# 6_FE-MISC.net
KiCad netlist of a schematic drawn in Altium Designer
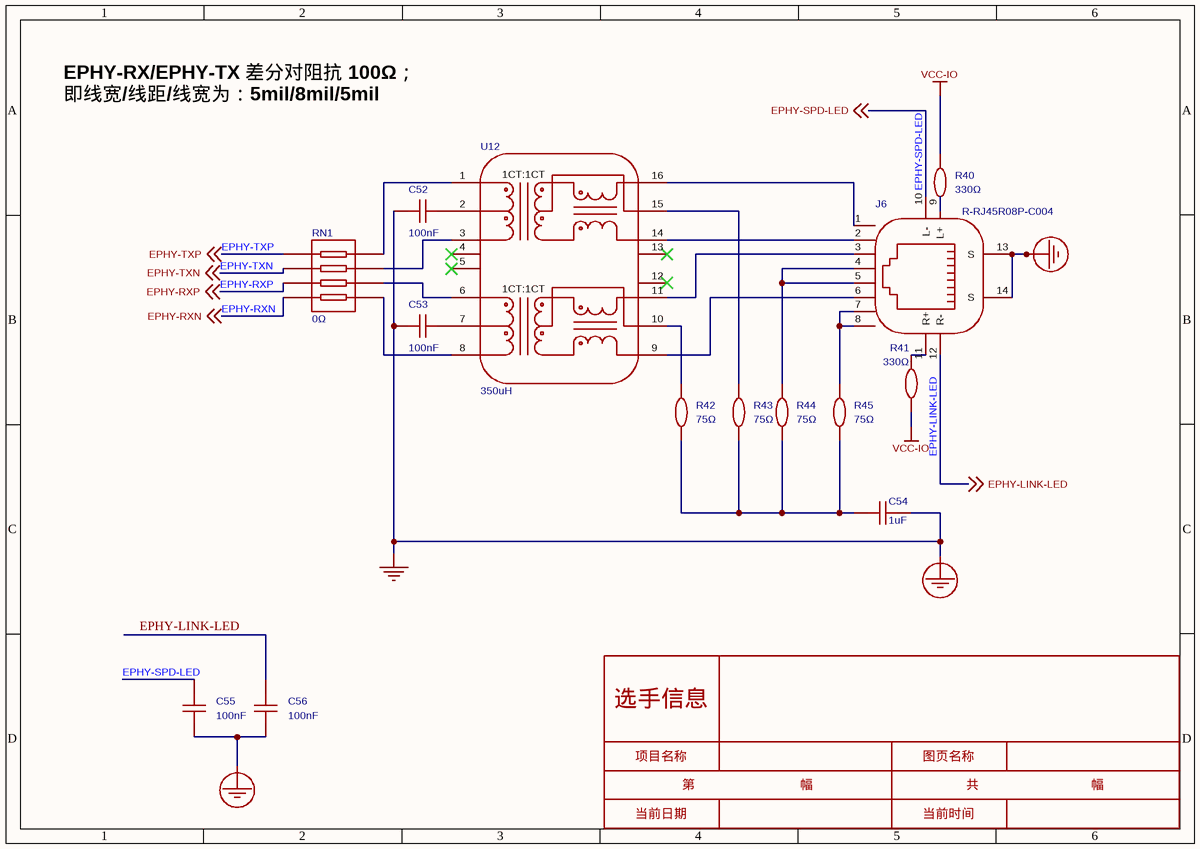
[diagram p0: 6_FE-MISC.schdoc]

(export (version "E")
  (design (tool "Eeschema 10.0.6"))
  (components
    (comp (ref "C52")
      (value "100nF")
      (footprint "C0402")
      (description "容值:100nF;精度:±10%;额定电压:16V;温度系数:X7R;")
      (fields
        (field (name "MANUFACTURER") "SAMSUNG(三星)")
        (field (name "MANUFACTURER PART") "CL05B104KO5NNNC")
      )
      (libsource (lib "altium-import") (part "root_2_CL05B104KO5NNNC_"))
    )
    (comp (ref "C53")
      (value "100nF")
      (footprint "C0402")
      (description "容值:100nF;精度:±10%;额定电压:16V;温度系数:X7R;")
      (fields
        (field (name "MANUFACTURER") "SAMSUNG(三星)")
        (field (name "MANUFACTURER PART") "CL05B104KO5NNNC")
      )
      (libsource (lib "altium-import") (part "root_2_CL05B104KO5NNNC_"))
    )
    (comp (ref "C54")
      (value "1uF")
      (footprint "C1206")
      (description "容值:1uF;精度:±10%;额定电压:50V;温度系数:X7R;")
      (fields (field (name "MANUFACTURER") "SAMSUNG(三星)") (field (name "MANUFACTURERPART") "CL31B105KBHNNNE"))
      (libsource (lib "altium-import") (part "root_0_CL31B105KBHNNNE_"))
    )
    (comp (ref "C55")
      (value "100nF")
      (footprint "C0402")
      (description "容值:100nF;精度:±10%;额定电压:16V;温度系数:X7R;")
      (fields
        (field (name "MANUFACTURER") "SAMSUNG(三星)")
        (field (name "MANUFACTURER PART") "CL05B104KO5NNNC")
      )
      (libsource (lib "altium-import") (part "root_1_CL05B104KO5NNNC_"))
    )
    (comp (ref "C56")
      (value "100nF")
      (footprint "C0402")
      (description "容值:100nF;精度:±10%;额定电压:16V;温度系数:X7R;")
      (fields
        (field (name "MANUFACTURER") "SAMSUNG(三星)")
        (field (name "MANUFACTURER PART") "CL05B104KO5NNNC")
      )
      (libsource (lib "altium-import") (part "root_1_CL05B104KO5NNNC_"))
    )
    (comp (ref "J6")
      (value "R-RJ45R08P-C004")
      (footprint "RJ45-TH_R-RJ45R08P-C004")
      (description "连接器类型:RJ45插座;安装方式:弯插;端口数量:1;LED:带LED;屏蔽:有屏蔽;等级:-;触头材质:磷青铜;触头镀层:金;工作温度:0℃~+70℃;")
      (fields (field (name "MANUFACTURER") "Ckmtw(灿科盟)"))
      (libsource (lib "altium-import") (part "root_3_R-RJ45R08P-C004_"))
    )
    (comp (ref "R40")
      (value "330Ω")
      (footprint "R0402")
      (description "电阻类型:厚膜电阻;阻值:330Ω;精度:±1%;功率:62.5mW;工作电压:50V;温度系数:±100ppm/℃;")
      (fields
        (field (name "MANUFACTURER") "UNI-ROYAL(厚声)")
        (field (name "MANUFACTURER PART") "0402WGF3300TCE")
      )
      (libsource (lib "altium-import") (part "root_3_0402WGF3300TCE_"))
    )
    (comp (ref "R41")
      (value "330Ω")
      (footprint "R0402")
      (description "电阻类型:厚膜电阻;阻值:330Ω;精度:±1%;功率:62.5mW;工作电压:50V;温度系数:±100ppm/℃;")
      (fields
        (field (name "MANUFACTURER") "UNI-ROYAL(厚声)")
        (field (name "MANUFACTURER PART") "0402WGF3300TCE")
      )
      (libsource (lib "altium-import") (part "root_1_0402WGF3300TCE_"))
    )
    (comp (ref "R42")
      (value "75Ω")
      (footprint "R0603")
      (description "电阻类型:厚膜电阻;阻值:75Ω;精度:±1%;功率:100mW;工作电压:75V;温度系数:±100ppm/℃;")
      (fields
        (field (name "MANUFACTURER") "UNI-ROYAL(厚声)")
        (field (name "MANUFACTURERPART") "0603WAF750JT5E")
      )
      (libsource (lib "altium-import") (part "root_1_0603WAF750JT5E_"))
    )
    (comp (ref "R43")
      (value "75Ω")
      (footprint "R0603")
      (description "电阻类型:厚膜电阻;阻值:75Ω;精度:±1%;功率:100mW;工作电压:75V;温度系数:±100ppm/℃;")
      (fields
        (field (name "MANUFACTURER") "UNI-ROYAL(厚声)")
        (field (name "MANUFACTURERPART") "0603WAF750JT5E")
      )
      (libsource (lib "altium-import") (part "root_1_0603WAF750JT5E_"))
    )
    (comp (ref "R44")
      (value "75Ω")
      (footprint "R0603")
      (description "电阻类型:厚膜电阻;阻值:75Ω;精度:±1%;功率:100mW;工作电压:75V;温度系数:±100ppm/℃;")
      (fields
        (field (name "MANUFACTURER") "UNI-ROYAL(厚声)")
        (field (name "MANUFACTURERPART") "0603WAF750JT5E")
      )
      (libsource (lib "altium-import") (part "root_1_0603WAF750JT5E_"))
    )
    (comp (ref "R45")
      (value "75Ω")
      (footprint "R0603")
      (description "电阻类型:厚膜电阻;阻值:75Ω;精度:±1%;功率:100mW;工作电压:75V;温度系数:±100ppm/℃;")
      (fields
        (field (name "MANUFACTURER") "UNI-ROYAL(厚声)")
        (field (name "MANUFACTURERPART") "0603WAF750JT5E")
      )
      (libsource (lib "altium-import") (part "root_1_0603WAF750JT5E_"))
    )
    (comp (ref "RN1")
      (value "0Ω")
      (footprint "RES-ARRAY-SMD_0603-8P-L3.2-W1.6-BL")
      (description "电阻器数:4;阻值:0Ω;精度:±5%;单个元件功率:62.5mW;温度系数:±400ppm/℃;")
      (fields
        (field (name "MANUFACTURER") "UNI-ROYAL(厚声)")
        (field (name "MANUFACTURERPART") "4D03WGJ0000T5E")
      )
      (libsource (lib "altium-import") (part "root_0_4D03WGJ0000T5E_"))
    )
    (comp (ref "U12")
      (value "350uH")
      (footprint "XFMR-SMD_16P-L12.7-W7.1-P1.27-LS9.4-BL")
      (description "匝数比:1CT:1CT;速率:10/100M;功能(POE或非POE):POE;")
      (fields
        (field (name "MANUFACTURER") "CND-tek(磁联达)")
        (field (name "MANUFACTURER PART") "PM44-11BP T-CND")
      )
      (libsource (lib "altium-import") (part "root_0_PM44-11BP T-CND_"))
    )
  )
  (nets
    (net (code "2") (name "EPHY-LINK-LED") (class "Default")
      (node (ref "C56") (pin "2") (pinfunction "2_2") (pintype "passive"))
      (node (ref "J6") (pin "12") (pinfunction "R-_12") (pintype "passive"))
    )
    (net (code "3") (name "EPHY-RXN") (class "Default")
      (node (ref "RN1") (pin "4") (pinfunction "4_4") (pintype "passive"))
    )
    (net (code "4") (name "EPHY-RXP") (class "Default")
      (node (ref "RN1") (pin "3") (pinfunction "3_3") (pintype "passive"))
    )
    (net (code "5") (name "EPHY-SPD-LED") (class "Default")
      (node (ref "C55") (pin "2") (pinfunction "2_2") (pintype "passive"))
      (node (ref "J6") (pin "10") (pinfunction "L-_10") (pintype "passive"))
    )
    (net (code "6") (name "EPHY-TXN") (class "Default")
      (node (ref "RN1") (pin "2") (pinfunction "2_2") (pintype "passive"))
    )
    (net (code "7") (name "EPHY-TXP") (class "Default")
      (node (ref "RN1") (pin "1") (pinfunction "1_1") (pintype "passive"))
    )
    (net (code "8") (name "GND") (class "Default")
      (node (ref "C52") (pin "2") (pinfunction "2_2") (pintype "passive"))
      (node (ref "C53") (pin "2") (pinfunction "2_2") (pintype "passive"))
      (node (ref "C54") (pin "2") (pinfunction "2_2") (pintype "passive"))
      (node (ref "C55") (pin "1") (pinfunction "1_1") (pintype "passive"))
      (node (ref "C56") (pin "1") (pinfunction "1_1") (pintype "passive"))
      (node (ref "J6") (pin "13") (pinfunction "S_13") (pintype "passive"))
      (node (ref "J6") (pin "14") (pinfunction "S_14") (pintype "passive"))
    )
    (net (code "9") (name "Net-(C52-Pad1)") (class "Default")
      (node (ref "C52") (pin "1") (pinfunction "1_1") (pintype "passive"))
      (node (ref "U12") (pin "2") (pinfunction "2_2") (pintype "passive"))
    )
    (net (code "10") (name "Net-(C53-Pad1)") (class "Default")
      (node (ref "C53") (pin "1") (pinfunction "1_1") (pintype "passive"))
      (node (ref "U12") (pin "7") (pinfunction "7_7") (pintype "passive"))
    )
    (net (code "11") (name "Net-(C54-Pad1)") (class "Default")
      (node (ref "C54") (pin "1") (pinfunction "1_1") (pintype "passive"))
      (node (ref "R42") (pin "1") (pinfunction "1_1") (pintype "passive"))
      (node (ref "R43") (pin "1") (pinfunction "1_1") (pintype "passive"))
      (node (ref "R44") (pin "1") (pinfunction "1_1") (pintype "passive"))
      (node (ref "R45") (pin "1") (pinfunction "1_1") (pintype "passive"))
    )
    (net (code "12") (name "Net-(J6-L+)") (class "Default")
      (node (ref "J6") (pin "9") (pinfunction "L+_9") (pintype "passive"))
      (node (ref "R40") (pin "2") (pinfunction "2_2") (pintype "passive"))
    )
    (net (code "13") (name "Net-(J6-Pad1)") (class "Default")
      (node (ref "J6") (pin "1") (pinfunction "1_1") (pintype "passive"))
      (node (ref "U12") (pin "16") (pinfunction "16_16") (pintype "passive"))
    )
    (net (code "14") (name "Net-(J6-Pad2)") (class "Default")
      (node (ref "J6") (pin "2") (pinfunction "2_2") (pintype "passive"))
      (node (ref "U12") (pin "14") (pinfunction "14_14") (pintype "passive"))
    )
    (net (code "15") (name "Net-(J6-Pad3)") (class "Default")
      (node (ref "J6") (pin "3") (pinfunction "3_3") (pintype "passive"))
      (node (ref "U12") (pin "11") (pinfunction "11_11") (pintype "passive"))
    )
    (net (code "16") (name "Net-(J6-Pad4)") (class "Default")
      (node (ref "J6") (pin "4") (pinfunction "4_4") (pintype "passive"))
      (node (ref "J6") (pin "5") (pinfunction "5_5") (pintype "passive"))
      (node (ref "R44") (pin "2") (pinfunction "2_2") (pintype "passive"))
    )
    (net (code "17") (name "Net-(J6-Pad6)") (class "Default")
      (node (ref "J6") (pin "6") (pinfunction "6_6") (pintype "passive"))
      (node (ref "U12") (pin "9") (pinfunction "9_9") (pintype "passive"))
    )
    (net (code "18") (name "Net-(J6-Pad7)") (class "Default")
      (node (ref "J6") (pin "7") (pinfunction "7_7") (pintype "passive"))
      (node (ref "J6") (pin "8") (pinfunction "8_8") (pintype "passive"))
      (node (ref "R45") (pin "2") (pinfunction "2_2") (pintype "passive"))
    )
    (net (code "19") (name "Net-(J6-R+)") (class "Default")
      (node (ref "J6") (pin "11") (pinfunction "R+_11") (pintype "passive"))
      (node (ref "R41") (pin "2") (pinfunction "2_2") (pintype "passive"))
    )
    (net (code "20") (name "Net-(R42-Pad2)") (class "Default")
      (node (ref "R42") (pin "2") (pinfunction "2_2") (pintype "passive"))
      (node (ref "U12") (pin "10") (pinfunction "10_10") (pintype "passive"))
    )
    (net (code "21") (name "Net-(R43-Pad2)") (class "Default")
      (node (ref "R43") (pin "2") (pinfunction "2_2") (pintype "passive"))
      (node (ref "U12") (pin "15") (pinfunction "15_15") (pintype "passive"))
    )
    (net (code "22") (name "Net-(RN1-Pad5)") (class "Default")
      (node (ref "RN1") (pin "5") (pinfunction "5_5") (pintype "passive"))
      (node (ref "U12") (pin "8") (pinfunction "8_8") (pintype "passive"))
    )
    (net (code "23") (name "Net-(RN1-Pad6)") (class "Default")
      (node (ref "RN1") (pin "6") (pinfunction "6_6") (pintype "passive"))
      (node (ref "U12") (pin "6") (pinfunction "6_6") (pintype "passive"))
    )
    (net (code "24") (name "Net-(RN1-Pad7)") (class "Default")
      (node (ref "RN1") (pin "7") (pinfunction "7_7") (pintype "passive"))
      (node (ref "U12") (pin "3") (pinfunction "3_3") (pintype "passive"))
    )
    (net (code "25") (name "Net-(RN1-Pad8)") (class "Default")
      (node (ref "RN1") (pin "8") (pinfunction "8_8") (pintype "passive"))
      (node (ref "U12") (pin "1") (pinfunction "1_1") (pintype "passive"))
    )
    (net (code "26") (name "VCC-IO") (class "Default")
      (node (ref "R40") (pin "1") (pinfunction "1_1") (pintype "passive"))
      (node (ref "R41") (pin "1") (pinfunction "1_1") (pintype "passive"))
    )
    (net (code "27") (name "unconnected-(U12-Pad4)") (class "Default")
      (node (ref "U12") (pin "4") (pinfunction "4_4") (pintype "passive+no_connect"))
    )
    (net (code "28") (name "unconnected-(U12-Pad5)") (class "Default")
      (node (ref "U12") (pin "5") (pinfunction "5_5") (pintype "passive+no_connect"))
    )
    (net (code "29") (name "unconnected-(U12-Pad12)") (class "Default")
      (node (ref "U12") (pin "12") (pinfunction "12_12") (pintype "passive+no_connect"))
    )
    (net (code "30") (name "unconnected-(U12-Pad13)") (class "Default")
      (node (ref "U12") (pin "13") (pinfunction "13_13") (pintype "passive+no_connect"))
    )
  )
)
